# PWR.net
KiCad netlist of a schematic drawn in Altium Designer
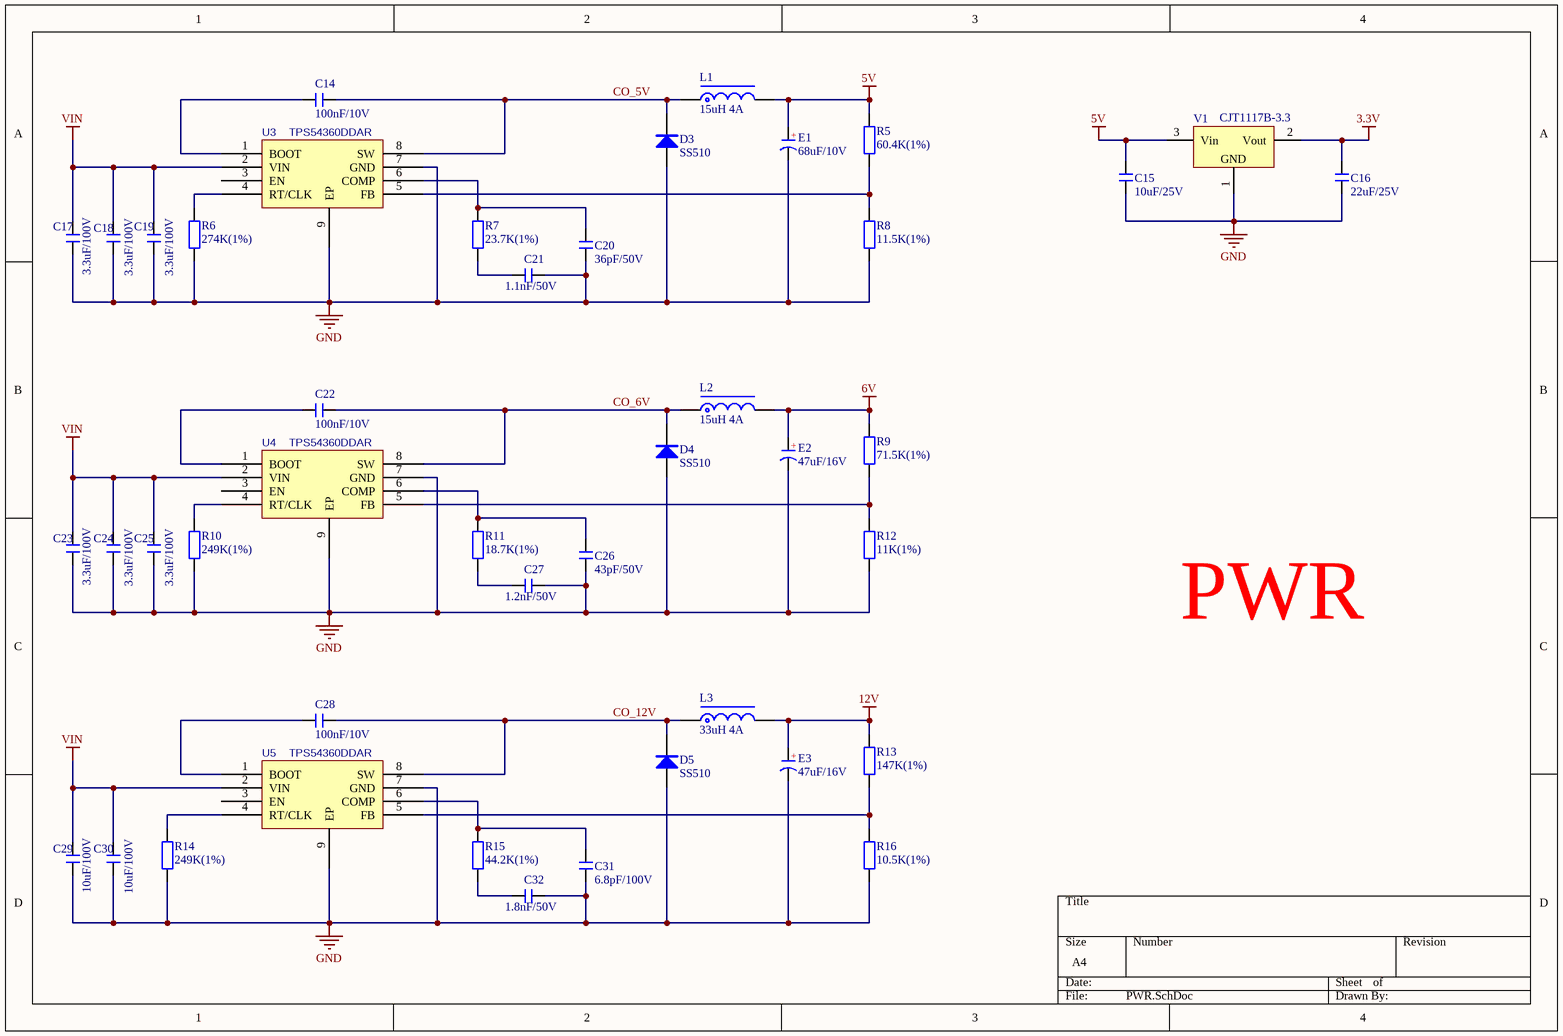
[diagram p0: PWR.SchDoc]

(export (version "E")
  (design (tool "Eeschema 10.0.6"))
  (components
    (comp (ref "C14")
      (value "100nF/10V")
      (footprint "C 0603_L")
      (description "无极性贴片电容")
      (fields (field (name "版权归属") "源创客"))
      (libsource (lib "电阻-电容-电感") (part "C"))
    )
    (comp (ref "C15")
      (value "10uF/25V")
      (footprint "C 0603_L")
      (description "无极性贴片电容")
      (fields (field (name "版权归属") "源创客"))
      (libsource (lib "电阻-电容-电感") (part "C"))
    )
    (comp (ref "C16")
      (value "22uF/25V")
      (footprint "C 0603_L")
      (description "无极性贴片电容")
      (fields (field (name "版权归属") "源创客"))
      (libsource (lib "电阻-电容-电感") (part "C"))
    )
    (comp (ref "C17")
      (value "3.3uF/100V")
      (footprint "C 1210_L")
      (description "无极性贴片电容")
      (fields (field (name "版权归属") "源创客"))
      (libsource (lib "电阻-电容-电感") (part "C"))
    )
    (comp (ref "C18")
      (value "3.3uF/100V")
      (footprint "C 1210_L")
      (description "无极性贴片电容")
      (fields (field (name "版权归属") "源创客"))
      (libsource (lib "电阻-电容-电感") (part "C"))
    )
    (comp (ref "C19")
      (value "3.3uF/100V")
      (footprint "C 1210_L")
      (description "无极性贴片电容")
      (fields (field (name "版权归属") "源创客"))
      (libsource (lib "电阻-电容-电感") (part "C"))
    )
    (comp (ref "C20")
      (value "36pF/50V")
      (footprint "C 0603_L")
      (description "无极性贴片电容")
      (fields (field (name "版权归属") "源创客"))
      (libsource (lib "电阻-电容-电感") (part "C"))
    )
    (comp (ref "C21")
      (value "1.1nF/50V")
      (footprint "C 0603_L")
      (description "无极性贴片电容")
      (fields (field (name "版权归属") "源创客"))
      (libsource (lib "电阻-电容-电感") (part "C"))
    )
    (comp (ref "C22")
      (value "100nF/10V")
      (footprint "C 0603_L")
      (description "无极性贴片电容")
      (fields (field (name "版权归属") "源创客"))
      (libsource (lib "电阻-电容-电感") (part "C"))
    )
    (comp (ref "C23")
      (value "3.3uF/100V")
      (footprint "C 1210_L")
      (description "无极性贴片电容")
      (fields (field (name "版权归属") "源创客"))
      (libsource (lib "电阻-电容-电感") (part "C"))
    )
    (comp (ref "C24")
      (value "3.3uF/100V")
      (footprint "C 1210_L")
      (description "无极性贴片电容")
      (fields (field (name "版权归属") "源创客"))
      (libsource (lib "电阻-电容-电感") (part "C"))
    )
    (comp (ref "C25")
      (value "3.3uF/100V")
      (footprint "C 1210_L")
      (description "无极性贴片电容")
      (fields (field (name "版权归属") "源创客"))
      (libsource (lib "电阻-电容-电感") (part "C"))
    )
    (comp (ref "C26")
      (value "43pF/50V")
      (footprint "C 0603_L")
      (description "无极性贴片电容")
      (fields (field (name "版权归属") "源创客"))
      (libsource (lib "电阻-电容-电感") (part "C"))
    )
    (comp (ref "C27")
      (value "1.2nF/50V")
      (footprint "C 0603_L")
      (description "无极性贴片电容")
      (fields (field (name "版权归属") "源创客"))
      (libsource (lib "电阻-电容-电感") (part "C"))
    )
    (comp (ref "C28")
      (value "100nF/10V")
      (footprint "C 0603_L")
      (description "无极性贴片电容")
      (fields (field (name "版权归属") "源创客"))
      (libsource (lib "电阻-电容-电感") (part "C"))
    )
    (comp (ref "C29")
      (value "10uF/100V")
      (footprint "C 1210_L")
      (description "无极性贴片电容")
      (fields (field (name "版权归属") "源创客"))
      (libsource (lib "电阻-电容-电感") (part "C"))
    )
    (comp (ref "C30")
      (value "10uF/100V")
      (footprint "C 1210_L")
      (description "无极性贴片电容")
      (fields (field (name "版权归属") "源创客"))
      (libsource (lib "电阻-电容-电感") (part "C"))
    )
    (comp (ref "C31")
      (value "6.8pF/100V")
      (footprint "C 0603_L")
      (description "无极性贴片电容")
      (fields (field (name "版权归属") "源创客"))
      (libsource (lib "电阻-电容-电感") (part "C"))
    )
    (comp (ref "C32")
      (value "1.8nF/50V")
      (footprint "C 0603_L")
      (description "无极性贴片电容")
      (fields (field (name "版权归属") "源创客"))
      (libsource (lib "电阻-电容-电感") (part "C"))
    )
    (comp (ref "D3")
      (value "SS510")
      (footprint "SMA")
      (description "肖特基二极管")
      (fields (field (name "版权归属") "源创客"))
      (libsource (lib "二极管-整流桥") (part "SS210"))
    )
    (comp (ref "D4")
      (value "SS510")
      (footprint "SMA")
      (description "肖特基二极管")
      (fields (field (name "版权归属") "源创客"))
      (libsource (lib "二极管-整流桥") (part "SS210"))
    )
    (comp (ref "D5")
      (value "SS510")
      (footprint "SMA")
      (description "肖特基二极管")
      (fields (field (name "版权归属") "源创客"))
      (libsource (lib "二极管-整流桥") (part "SS210"))
    )
    (comp (ref "E1")
      (value "68uF/10V")
      (footprint "CD B(3528)")
      (description "贴片钽电容")
      (fields (field (name "版权归属") "源创客"))
      (libsource (lib "电阻-电容-电感") (part "C-CD"))
    )
    (comp (ref "E2")
      (value "47uF/16V")
      (footprint "CD B(3528)")
      (description "贴片钽电容")
      (fields (field (name "版权归属") "源创客"))
      (libsource (lib "电阻-电容-电感") (part "C-CD"))
    )
    (comp (ref "E3")
      (value "47uF/16V")
      (footprint "CD B(3528)")
      (description "贴片钽电容")
      (fields (field (name "版权归属") "源创客"))
      (libsource (lib "电阻-电容-电感") (part "C-CD"))
    )
    (comp (ref "L1")
      (value "15uH 4A")
      (footprint "L-SMD-1040")
      (description "一体成型电感")
      (fields (field (name "版权归属") "源创客"))
      (libsource (lib "电阻-电容-电感") (part "L-CDRH"))
    )
    (comp (ref "L2")
      (value "15uH 4A")
      (footprint "L-SMD-1040")
      (description "一体成型电感")
      (fields (field (name "版权归属") "源创客"))
      (libsource (lib "电阻-电容-电感") (part "L-CDRH"))
    )
    (comp (ref "L3")
      (value "33uH 4A")
      (footprint "L-SMD-1040")
      (description "一体成型电感")
      (fields (field (name "版权归属") "源创客"))
      (libsource (lib "电阻-电容-电感") (part "L-CDRH"))
    )
    (comp (ref "R5")
      (value "60.4K(1%)")
      (footprint "R 0603_L")
      (description "贴片电阻")
      (fields (field (name "版权归属") "源创客"))
      (libsource (lib "电阻-电容-电感") (part "R"))
    )
    (comp (ref "R6")
      (value "274K(1%)")
      (footprint "R 0603_L")
      (description "贴片电阻")
      (fields (field (name "版权归属") "源创客"))
      (libsource (lib "电阻-电容-电感") (part "R"))
    )
    (comp (ref "R7")
      (value "23.7K(1%)")
      (footprint "R 0603_L")
      (description "贴片电阻")
      (fields (field (name "版权归属") "源创客"))
      (libsource (lib "电阻-电容-电感") (part "R"))
    )
    (comp (ref "R8")
      (value "11.5K(1%)")
      (footprint "R 0603_L")
      (description "贴片电阻")
      (fields (field (name "版权归属") "源创客"))
      (libsource (lib "电阻-电容-电感") (part "R"))
    )
    (comp (ref "R9")
      (value "71.5K(1%)")
      (footprint "R 0603_L")
      (description "贴片电阻")
      (fields (field (name "版权归属") "源创客"))
      (libsource (lib "电阻-电容-电感") (part "R"))
    )
    (comp (ref "R10")
      (value "249K(1%)")
      (footprint "R 0603_L")
      (description "贴片电阻")
      (fields (field (name "版权归属") "源创客"))
      (libsource (lib "电阻-电容-电感") (part "R"))
    )
    (comp (ref "R11")
      (value "18.7K(1%)")
      (footprint "R 0603_L")
      (description "贴片电阻")
      (fields (field (name "版权归属") "源创客"))
      (libsource (lib "电阻-电容-电感") (part "R"))
    )
    (comp (ref "R12")
      (value "11K(1%)")
      (footprint "R 0603_L")
      (description "贴片电阻")
      (fields (field (name "版权归属") "源创客"))
      (libsource (lib "电阻-电容-电感") (part "R"))
    )
    (comp (ref "R13")
      (value "147K(1%)")
      (footprint "R 0603_L")
      (description "贴片电阻")
      (fields (field (name "版权归属") "源创客"))
      (libsource (lib "电阻-电容-电感") (part "R"))
    )
    (comp (ref "R14")
      (value "249K(1%)")
      (footprint "R 0603_L")
      (description "贴片电阻")
      (fields (field (name "版权归属") "源创客"))
      (libsource (lib "电阻-电容-电感") (part "R"))
    )
    (comp (ref "R15")
      (value "44.2K(1%)")
      (footprint "R 0603_L")
      (description "贴片电阻")
      (fields (field (name "版权归属") "源创客"))
      (libsource (lib "电阻-电容-电感") (part "R"))
    )
    (comp (ref "R16")
      (value "10.5K(1%)")
      (footprint "R 0603_L")
      (description "贴片电阻")
      (fields (field (name "版权归属") "源创客"))
      (libsource (lib "电阻-电容-电感") (part "R"))
    )
    (comp (ref "U3")
      (value "TPS54360DDAR")
      (footprint "SOP-8EP")
      (fields (field (name "BOM_SUPPLIER PART") "C44377"))
      (libsource (lib "MICB") (part "TPS54360DDAR"))
    )
    (comp (ref "U4")
      (value "TPS54360DDAR")
      (footprint "SOP-8EP")
      (fields (field (name "BOM_SUPPLIER PART") "C44377"))
      (libsource (lib "MICB") (part "TPS54360DDAR"))
    )
    (comp (ref "U5")
      (value "TPS54360DDAR")
      (footprint "SOP-8EP")
      (fields (field (name "BOM_SUPPLIER PART") "C44377"))
      (libsource (lib "MICB") (part "TPS54360DDAR"))
    )
    (comp (ref "V1")
      (value "CJT1117B-3.3")
      (footprint "SOT223_L")
      (description "三端稳压芯片")
      (fields (field (name "版权归属") "源创客"))
      (libsource (lib "电源类芯片") (part "AMS1117"))
    )
  )
  (nets
    (net (code "1") (name "/CO_5V") (class "Default")
      (node (ref "C14") (pin "1") (pinfunction "1_1") (pintype "passive"))
      (node (ref "D3") (pin "2") (pinfunction "K_2") (pintype "passive"))
      (node (ref "L1") (pin "1") (pinfunction "1_1") (pintype "passive"))
      (node (ref "U3") (pin "8") (pinfunction "SW_8") (pintype "passive"))
    )
    (net (code "2") (name "/CO_6V") (class "Default")
      (node (ref "C22") (pin "1") (pinfunction "1_1") (pintype "passive"))
      (node (ref "D4") (pin "2") (pinfunction "K_2") (pintype "passive"))
      (node (ref "L2") (pin "1") (pinfunction "1_1") (pintype "passive"))
      (node (ref "U4") (pin "8") (pinfunction "SW_8") (pintype "passive"))
    )
    (net (code "3") (name "/CO_12V") (class "Default")
      (node (ref "C28") (pin "1") (pinfunction "1_1") (pintype "passive"))
      (node (ref "D5") (pin "2") (pinfunction "K_2") (pintype "passive"))
      (node (ref "L3") (pin "1") (pinfunction "1_1") (pintype "passive"))
      (node (ref "U5") (pin "8") (pinfunction "SW_8") (pintype "passive"))
    )
    (net (code "4") (name "3.3V") (class "Default")
      (node (ref "C16") (pin "2") (pinfunction "2_2") (pintype "passive"))
      (node (ref "V1") (pin "2") (pinfunction "Vout_2") (pintype "passive"))
    )
    (net (code "5") (name "5V") (class "Default")
      (node (ref "C15") (pin "2") (pinfunction "2_2") (pintype "passive"))
      (node (ref "E1") (pin "1") (pinfunction "A_1") (pintype "passive"))
      (node (ref "L1") (pin "2") (pinfunction "2_2") (pintype "passive"))
      (node (ref "R5") (pin "2") (pinfunction "2_2") (pintype "passive"))
      (node (ref "V1") (pin "3") (pinfunction "Vin_3") (pintype "passive"))
    )
    (net (code "6") (name "6V") (class "Default")
      (node (ref "E2") (pin "1") (pinfunction "A_1") (pintype "passive"))
      (node (ref "L2") (pin "2") (pinfunction "2_2") (pintype "passive"))
      (node (ref "R9") (pin "2") (pinfunction "2_2") (pintype "passive"))
    )
    (net (code "7") (name "12V") (class "Default")
      (node (ref "E3") (pin "1") (pinfunction "A_1") (pintype "passive"))
      (node (ref "L3") (pin "2") (pinfunction "2_2") (pintype "passive"))
      (node (ref "R13") (pin "2") (pinfunction "2_2") (pintype "passive"))
    )
    (net (code "8") (name "GND") (class "Default")
      (node (ref "C15") (pin "1") (pinfunction "1_1") (pintype "passive"))
      (node (ref "C16") (pin "1") (pinfunction "1_1") (pintype "passive"))
      (node (ref "C17") (pin "1") (pinfunction "1_1") (pintype "passive"))
      (node (ref "C18") (pin "1") (pinfunction "1_1") (pintype "passive"))
      (node (ref "C19") (pin "1") (pinfunction "1_1") (pintype "passive"))
      (node (ref "C20") (pin "2") (pinfunction "2_2") (pintype "passive"))
      (node (ref "C21") (pin "2") (pinfunction "2_2") (pintype "passive"))
      (node (ref "C23") (pin "1") (pinfunction "1_1") (pintype "passive"))
      (node (ref "C24") (pin "1") (pinfunction "1_1") (pintype "passive"))
      (node (ref "C25") (pin "1") (pinfunction "1_1") (pintype "passive"))
      (node (ref "C26") (pin "2") (pinfunction "2_2") (pintype "passive"))
      (node (ref "C27") (pin "2") (pinfunction "2_2") (pintype "passive"))
      (node (ref "C29") (pin "1") (pinfunction "1_1") (pintype "passive"))
      (node (ref "C30") (pin "1") (pinfunction "1_1") (pintype "passive"))
      (node (ref "C31") (pin "2") (pinfunction "2_2") (pintype "passive"))
      (node (ref "C32") (pin "2") (pinfunction "2_2") (pintype "passive"))
      (node (ref "D3") (pin "1") (pinfunction "A_1") (pintype "passive"))
      (node (ref "D4") (pin "1") (pinfunction "A_1") (pintype "passive"))
      (node (ref "D5") (pin "1") (pinfunction "A_1") (pintype "passive"))
      (node (ref "E1") (pin "2") (pinfunction "K_2") (pintype "passive"))
      (node (ref "E2") (pin "2") (pinfunction "K_2") (pintype "passive"))
      (node (ref "E3") (pin "2") (pinfunction "K_2") (pintype "passive"))
      (node (ref "R10") (pin "1") (pinfunction "1_1") (pintype "passive"))
      (node (ref "R12") (pin "1") (pinfunction "1_1") (pintype "passive"))
      (node (ref "R14") (pin "1") (pinfunction "1_1") (pintype "passive"))
      (node (ref "R16") (pin "1") (pinfunction "1_1") (pintype "passive"))
      (node (ref "R6") (pin "1") (pinfunction "1_1") (pintype "passive"))
      (node (ref "R8") (pin "1") (pinfunction "1_1") (pintype "passive"))
      (node (ref "U3") (pin "7") (pinfunction "GND_7") (pintype "passive"))
      (node (ref "U3") (pin "9") (pinfunction "EP_9") (pintype "passive"))
      (node (ref "U4") (pin "7") (pinfunction "GND_7") (pintype "passive"))
      (node (ref "U4") (pin "9") (pinfunction "EP_9") (pintype "passive"))
      (node (ref "U5") (pin "7") (pinfunction "GND_7") (pintype "passive"))
      (node (ref "U5") (pin "9") (pinfunction "EP_9") (pintype "passive"))
      (node (ref "V1") (pin "1") (pinfunction "GND_1") (pintype "passive"))
    )
    (net (code "9") (name "Net-(C21-Pad1)") (class "Default")
      (node (ref "C21") (pin "1") (pinfunction "1_1") (pintype "passive"))
      (node (ref "R7") (pin "1") (pinfunction "1_1") (pintype "passive"))
    )
    (net (code "10") (name "Net-(C27-Pad1)") (class "Default")
      (node (ref "C27") (pin "1") (pinfunction "1_1") (pintype "passive"))
      (node (ref "R11") (pin "1") (pinfunction "1_1") (pintype "passive"))
    )
    (net (code "11") (name "Net-(C32-Pad1)") (class "Default")
      (node (ref "C32") (pin "1") (pinfunction "1_1") (pintype "passive"))
      (node (ref "R15") (pin "1") (pinfunction "1_1") (pintype "passive"))
    )
    (net (code "12") (name "Net-(U3-BOOT)") (class "Default")
      (node (ref "C14") (pin "2") (pinfunction "2_2") (pintype "passive"))
      (node (ref "U3") (pin "1") (pinfunction "BOOT_1") (pintype "passive"))
    )
    (net (code "13") (name "Net-(U3-COMP)") (class "Default")
      (node (ref "C20") (pin "1") (pinfunction "1_1") (pintype "passive"))
      (node (ref "R7") (pin "2") (pinfunction "2_2") (pintype "passive"))
      (node (ref "U3") (pin "6") (pinfunction "COMP_6") (pintype "passive"))
    )
    (net (code "14") (name "Net-(U3-FB)") (class "Default")
      (node (ref "R5") (pin "1") (pinfunction "1_1") (pintype "passive"))
      (node (ref "R8") (pin "2") (pinfunction "2_2") (pintype "passive"))
      (node (ref "U3") (pin "5") (pinfunction "FB_5") (pintype "passive"))
    )
    (net (code "15") (name "Net-(U3-RT{slash}CLK)") (class "Default")
      (node (ref "R6") (pin "2") (pinfunction "2_2") (pintype "passive"))
      (node (ref "U3") (pin "4") (pinfunction "RT/CLK_4") (pintype "passive"))
    )
    (net (code "16") (name "Net-(U4-BOOT)") (class "Default")
      (node (ref "C22") (pin "2") (pinfunction "2_2") (pintype "passive"))
      (node (ref "U4") (pin "1") (pinfunction "BOOT_1") (pintype "passive"))
    )
    (net (code "17") (name "Net-(U4-COMP)") (class "Default")
      (node (ref "C26") (pin "1") (pinfunction "1_1") (pintype "passive"))
      (node (ref "R11") (pin "2") (pinfunction "2_2") (pintype "passive"))
      (node (ref "U4") (pin "6") (pinfunction "COMP_6") (pintype "passive"))
    )
    (net (code "18") (name "Net-(U4-FB)") (class "Default")
      (node (ref "R12") (pin "2") (pinfunction "2_2") (pintype "passive"))
      (node (ref "R9") (pin "1") (pinfunction "1_1") (pintype "passive"))
      (node (ref "U4") (pin "5") (pinfunction "FB_5") (pintype "passive"))
    )
    (net (code "19") (name "Net-(U4-RT{slash}CLK)") (class "Default")
      (node (ref "R10") (pin "2") (pinfunction "2_2") (pintype "passive"))
      (node (ref "U4") (pin "4") (pinfunction "RT/CLK_4") (pintype "passive"))
    )
    (net (code "20") (name "Net-(U5-BOOT)") (class "Default")
      (node (ref "C28") (pin "2") (pinfunction "2_2") (pintype "passive"))
      (node (ref "U5") (pin "1") (pinfunction "BOOT_1") (pintype "passive"))
    )
    (net (code "21") (name "Net-(U5-COMP)") (class "Default")
      (node (ref "C31") (pin "1") (pinfunction "1_1") (pintype "passive"))
      (node (ref "R15") (pin "2") (pinfunction "2_2") (pintype "passive"))
      (node (ref "U5") (pin "6") (pinfunction "COMP_6") (pintype "passive"))
    )
    (net (code "22") (name "Net-(U5-FB)") (class "Default")
      (node (ref "R13") (pin "1") (pinfunction "1_1") (pintype "passive"))
      (node (ref "R16") (pin "2") (pinfunction "2_2") (pintype "passive"))
      (node (ref "U5") (pin "5") (pinfunction "FB_5") (pintype "passive"))
    )
    (net (code "23") (name "Net-(U5-RT{slash}CLK)") (class "Default")
      (node (ref "R14") (pin "2") (pinfunction "2_2") (pintype "passive"))
      (node (ref "U5") (pin "4") (pinfunction "RT/CLK_4") (pintype "passive"))
    )
    (net (code "24") (name "VIN") (class "Default")
      (node (ref "C17") (pin "2") (pinfunction "2_2") (pintype "passive"))
      (node (ref "C18") (pin "2") (pinfunction "2_2") (pintype "passive"))
      (node (ref "C19") (pin "2") (pinfunction "2_2") (pintype "passive"))
      (node (ref "C23") (pin "2") (pinfunction "2_2") (pintype "passive"))
      (node (ref "C24") (pin "2") (pinfunction "2_2") (pintype "passive"))
      (node (ref "C25") (pin "2") (pinfunction "2_2") (pintype "passive"))
      (node (ref "C29") (pin "2") (pinfunction "2_2") (pintype "passive"))
      (node (ref "C30") (pin "2") (pinfunction "2_2") (pintype "passive"))
      (node (ref "U3") (pin "2") (pinfunction "VIN_2") (pintype "passive"))
      (node (ref "U4") (pin "2") (pinfunction "VIN_2") (pintype "passive"))
      (node (ref "U5") (pin "2") (pinfunction "VIN_2") (pintype "passive"))
    )
    (net (code "25") (name "unconnected-(U3-EN-Pad3)") (class "Default")
      (node (ref "U3") (pin "3") (pinfunction "EN_3") (pintype "passive"))
    )
    (net (code "26") (name "unconnected-(U4-EN-Pad3)") (class "Default")
      (node (ref "U4") (pin "3") (pinfunction "EN_3") (pintype "passive"))
    )
    (net (code "27") (name "unconnected-(U5-EN-Pad3)") (class "Default")
      (node (ref "U5") (pin "3") (pinfunction "EN_3") (pintype "passive"))
    )
  )
)
